# mcu.net
KiCad netlist of a schematic drawn in Altium Designer
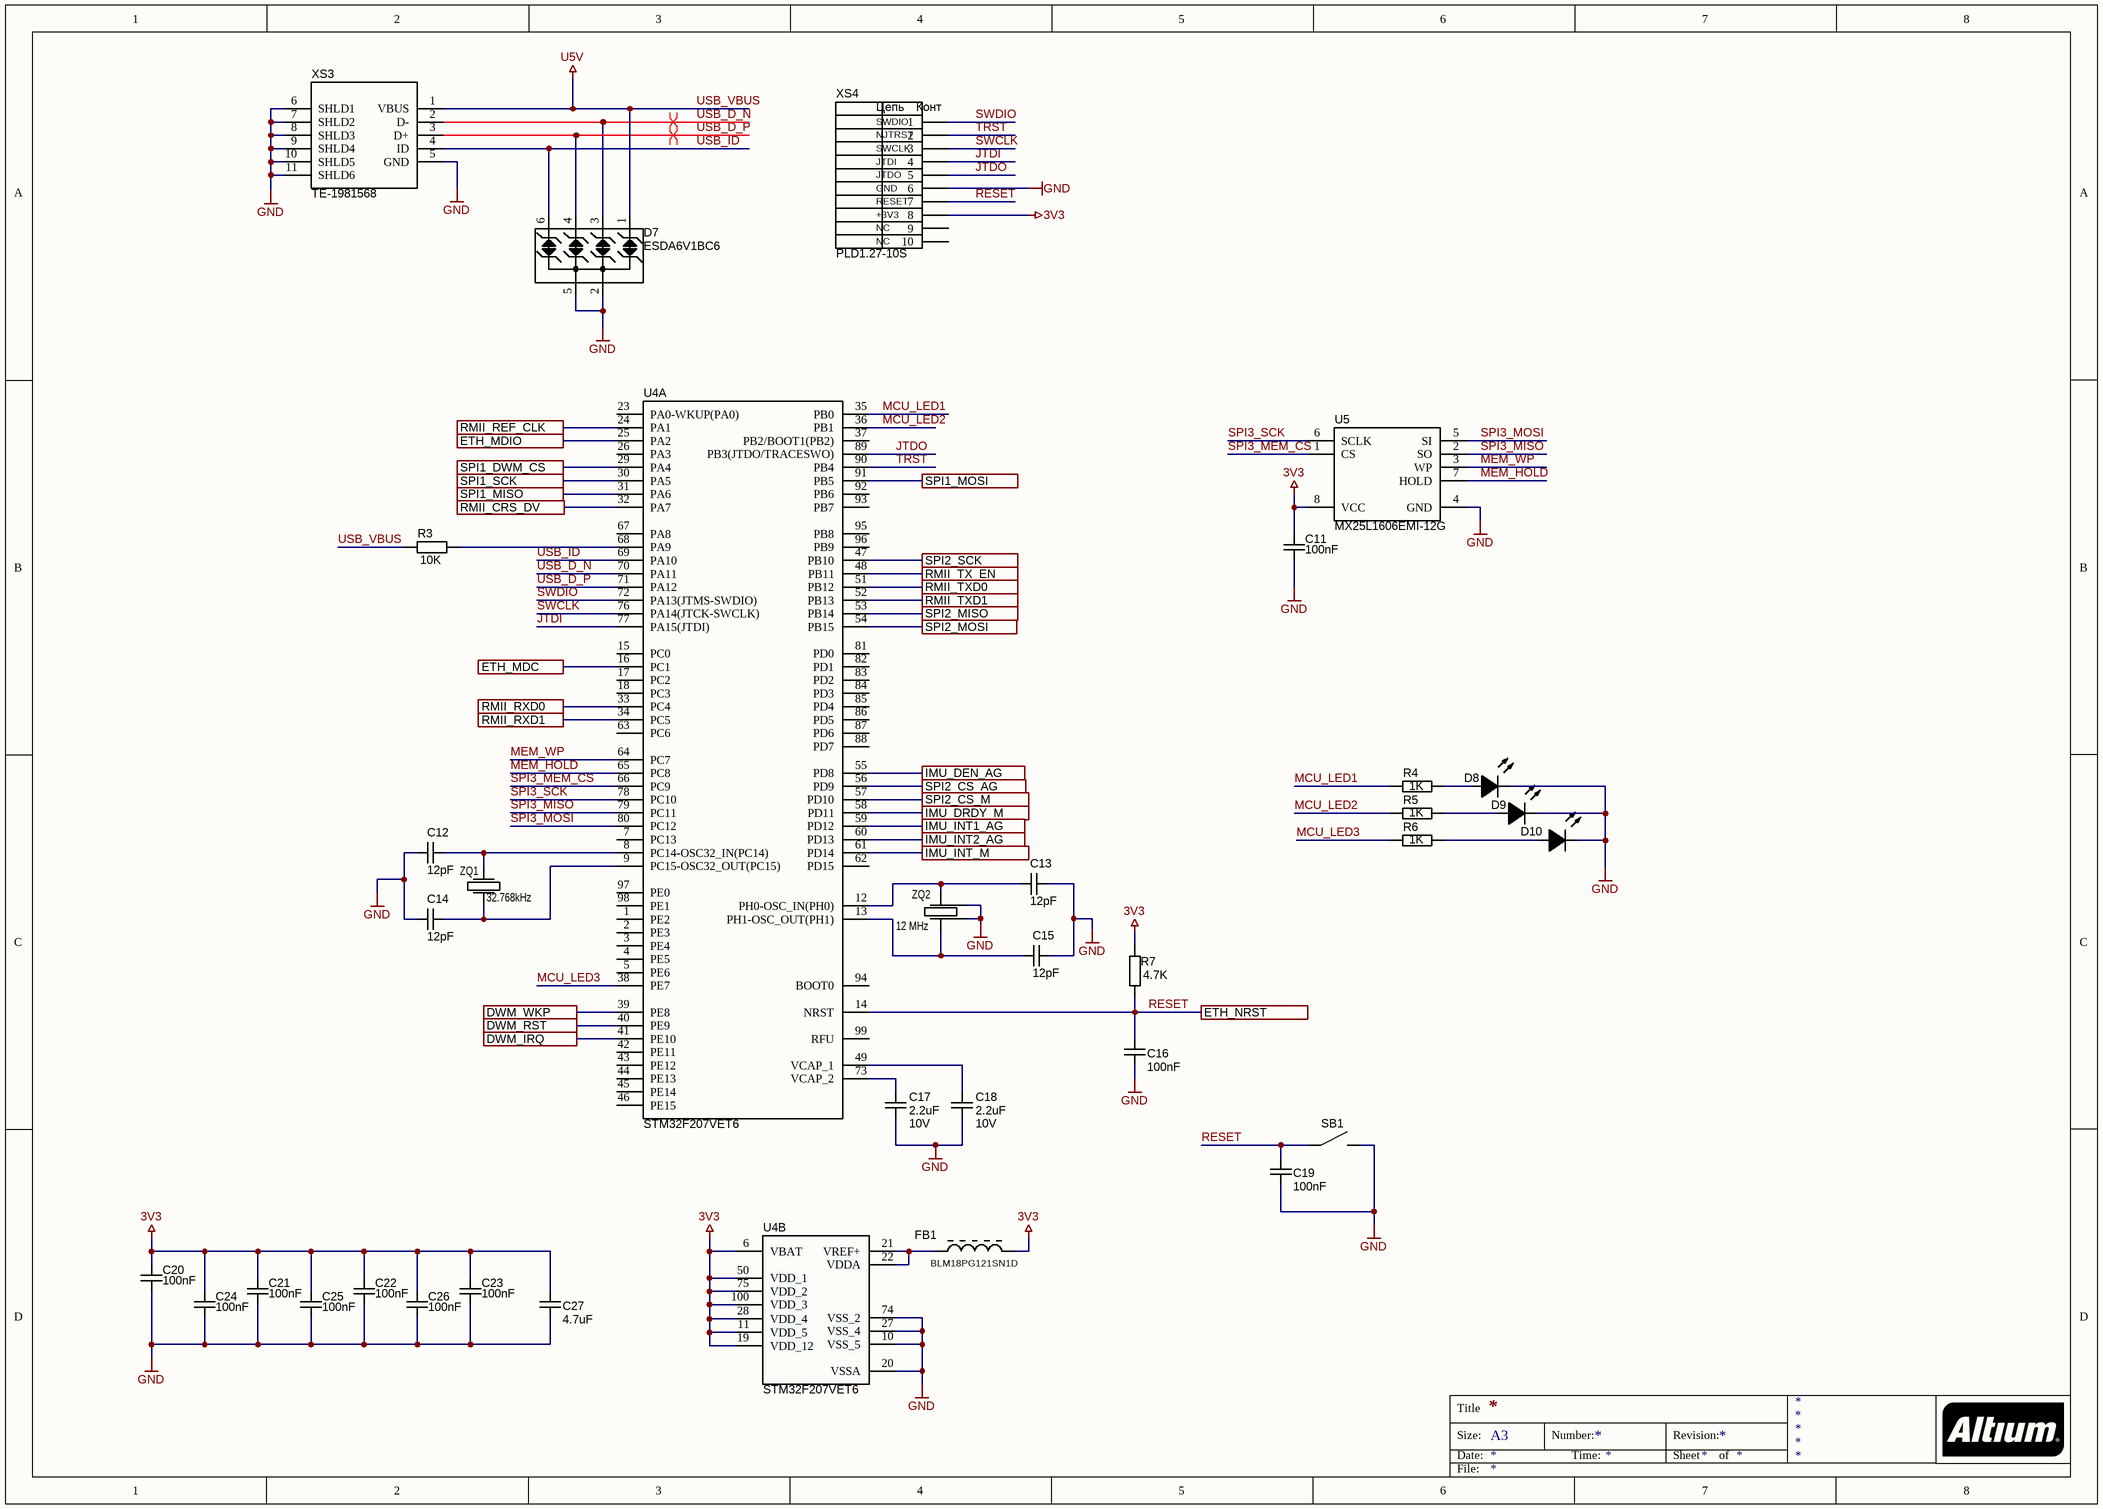
[diagram p0: mcu.SchDoc]

(export (version "E")
  (design (tool "Eeschema 10.0.6"))
  (components
    (comp (ref "C11")
      (value "100nF")
      (footprint "C0603")
      (fields (field (name "VOLTAGE") "10V") (field (name "Comment") "C0603"))
      (libsource (lib "DZ_LIB") (part "C0603"))
    )
    (comp (ref "C12")
      (value "12pF")
      (footprint "C0603")
      (fields (field (name "VOLTAGE") "*V") (field (name "Comment") "C0603"))
      (libsource (lib "DZ_LIB") (part "C0603"))
    )
    (comp (ref "C13")
      (value "12pF")
      (footprint "C0603")
      (fields (field (name "VOLTAGE") "10V") (field (name "Comment") "C0603"))
      (libsource (lib "DZ_LIB") (part "C0603"))
    )
    (comp (ref "C14")
      (value "12pF")
      (footprint "C0603")
      (fields (field (name "VOLTAGE") "*V") (field (name "Comment") "C0603"))
      (libsource (lib "DZ_LIB") (part "C0603"))
    )
    (comp (ref "C15")
      (value "12pF")
      (footprint "C0603")
      (fields (field (name "VOLTAGE") "10V") (field (name "Comment") "C0603"))
      (libsource (lib "DZ_LIB") (part "C0603"))
    )
    (comp (ref "C16")
      (value "100nF")
      (footprint "C0603")
      (fields (field (name "VOLTAGE") "10V") (field (name "Comment") "C0603"))
      (libsource (lib "DZ_LIB") (part "C0603"))
    )
    (comp (ref "C17")
      (value "2.2uF")
      (footprint "C1206(3216)")
      (fields (field (name "VOLTAGE") "10V") (field (name "Comment") "C1206"))
      (libsource (lib "DZ_LIB") (part "C1206"))
    )
    (comp (ref "C18")
      (value "2.2uF")
      (footprint "C1206(3216)")
      (fields (field (name "VOLTAGE") "10V") (field (name "Comment") "C1206"))
      (libsource (lib "DZ_LIB") (part "C1206"))
    )
    (comp (ref "C19")
      (value "100nF")
      (footprint "C0603")
      (fields (field (name "VOLTAGE") "10V") (field (name "Comment") "C0603"))
      (libsource (lib "DZ_LIB") (part "C0603"))
    )
    (comp (ref "C20")
      (value "100nF")
      (footprint "C0603")
      (fields (field (name "VOLTAGE") "10V") (field (name "Comment") "C0603"))
      (libsource (lib "DZ_LIB") (part "C0603"))
    )
    (comp (ref "C21")
      (value "100nF")
      (footprint "C0603")
      (fields (field (name "VOLTAGE") "10V") (field (name "Comment") "C0603"))
      (libsource (lib "DZ_LIB") (part "C0603"))
    )
    (comp (ref "C22")
      (value "100nF")
      (footprint "C0603")
      (fields (field (name "VOLTAGE") "10V") (field (name "Comment") "C0603"))
      (libsource (lib "DZ_LIB") (part "C0603"))
    )
    (comp (ref "C23")
      (value "100nF")
      (footprint "C0603")
      (fields (field (name "VOLTAGE") "10V") (field (name "Comment") "C0603"))
      (libsource (lib "DZ_LIB") (part "C0603"))
    )
    (comp (ref "C24")
      (value "100nF")
      (footprint "C0603")
      (fields (field (name "VOLTAGE") "10V") (field (name "Comment") "C0603"))
      (libsource (lib "DZ_LIB") (part "C0603"))
    )
    (comp (ref "C25")
      (value "100nF")
      (footprint "C0603")
      (fields (field (name "VOLTAGE") "10V") (field (name "Comment") "C0603"))
      (libsource (lib "DZ_LIB") (part "C0603"))
    )
    (comp (ref "C26")
      (value "100nF")
      (footprint "C0603")
      (fields (field (name "VOLTAGE") "10V") (field (name "Comment") "C0603"))
      (libsource (lib "DZ_LIB") (part "C0603"))
    )
    (comp (ref "C27")
      (value "4.7uF")
      (footprint "C0603")
      (fields (field (name "VOLTAGE") "10V") (field (name "Comment") "C0603"))
      (libsource (lib "DZ_LIB") (part "C0603"))
    )
    (comp (ref "D7")
      (value "ESDA6V1BC6")
      (footprint "SOT-23-6")
      (description "4-line ESD protection")
      (libsource (lib "DZ_LIB") (part "ESDA6V1BC6"))
    )
    (comp (ref "D8")
      (value "LED0805")
      (footprint "LED0805")
      (description "LED SMD 0805 K1A2")
      (libsource (lib "DZ_LIB") (part "LED0805"))
    )
    (comp (ref "D9")
      (value "LED0805")
      (footprint "LED0805")
      (description "LED SMD 0805 K1A2")
      (libsource (lib "DZ_LIB") (part "LED0805"))
    )
    (comp (ref "D10")
      (value "LED0805")
      (footprint "LED0805")
      (description "LED SMD 0805 K1A2")
      (libsource (lib "DZ_LIB") (part "LED0805"))
    )
    (comp (ref "FB1")
      (value "BLM18PG121SN1D")
      (footprint "BLM18")
      (description "Ferrite Bead 0603")
      (libsource (lib "DZ_LIB") (part "BLM18"))
    )
    (comp (ref "R3") (value "10K") (footprint "SMD0603") (libsource (lib "DZ_LIB") (part "R0603")))
    (comp (ref "R4") (value "1K") (footprint "SMD0603") (libsource (lib "") (part "R0603_1")))
    (comp (ref "R5") (value "1K") (footprint "SMD0603") (libsource (lib "") (part "R0603_1")))
    (comp (ref "R6") (value "1K") (footprint "SMD0603") (libsource (lib "") (part "R0603_1")))
    (comp (ref "R7")
      (value "4.7K")
      (footprint "SMD0603")
      (fields (field (name "Comment") "R0603"))
      (libsource (lib "") (part "R0603_2"))
    )
    (comp (ref "SB1")
      (value "FSMSM")
      (footprint "FSMSM-2")
      (description "SMD Switch 2-Leads")
      (libsource (lib "DZ_LIB") (part "FSMSM"))
    )
    (comp (ref "U4")
      (value "STM32F207VET6")
      (footprint "STM-LQFP100_V")
      (libsource (lib "DZ_LIB") (part "STM32F207VET6"))
    )
    (comp (ref "U5")
      (value "MX25L1606EMI-12G")
      (footprint "SOP-8")
      (description "FLASH 16M SPI 86MHZ 16SOP")
      (libsource (lib "DZ_LIB") (part "MX25L1606EMI-12G"))
    )
    (comp (ref "XS3")
      (value "TE-1981568")
      (footprint "TECO-1981568-5_V")
      (libsource (lib "DZ_LIB") (part "USB-Micro B"))
    )
    (comp (ref "XS4")
      (value "PLD1.27-10S")
      (footprint "PLD1.27-10S")
      (libsource (lib "DZ_LIB") (part "PLD1.27-10-MCU"))
    )
    (comp (ref "ZQ1")
      (value "32.768kHz")
      (footprint "DST210A")
      (description "DST210A")
      (libsource (lib "DZ_LIB") (part "Crystal"))
    )
    (comp (ref "ZQ2")
      (value "12 MHz")
      (footprint "NX3225")
      (description "DSX321G")
      (libsource (lib "DZ_LIB") (part "Crystal_4"))
    )
  )
  (nets
    (net (code "1") (name "/DWM_IRQ") (class "Default")
      (node (ref "U4") (pin "41") (pinfunction "PE10_41") (pintype "passive"))
    )
    (net (code "2") (name "/DWM_RST") (class "Default")
      (node (ref "U4") (pin "40") (pinfunction "PE9_40") (pintype "passive"))
    )
    (net (code "3") (name "/DWM_WKP") (class "Default")
      (node (ref "U4") (pin "39") (pinfunction "PE8_39") (pintype "passive"))
    )
    (net (code "4") (name "/ETH_MDC") (class "Default")
      (node (ref "U4") (pin "16") (pinfunction "PC1_16") (pintype "passive"))
    )
    (net (code "5") (name "/ETH_MDIO") (class "Default")
      (node (ref "U4") (pin "25") (pinfunction "PA2_25") (pintype "passive"))
    )
    (net (code "6") (name "/IMU_DEN_AG") (class "Default")
      (node (ref "U4") (pin "55") (pinfunction "PD8_55") (pintype "passive"))
    )
    (net (code "7") (name "/IMU_DRDY_M") (class "Default")
      (node (ref "U4") (pin "58") (pinfunction "PD11_58") (pintype "passive"))
    )
    (net (code "8") (name "/IMU_INT1_AG") (class "Default")
      (node (ref "U4") (pin "59") (pinfunction "PD12_59") (pintype "passive"))
    )
    (net (code "9") (name "/IMU_INT2_AG") (class "Default")
      (node (ref "U4") (pin "60") (pinfunction "PD13_60") (pintype "passive"))
    )
    (net (code "10") (name "/IMU_INT_M") (class "Default")
      (node (ref "U4") (pin "61") (pinfunction "PD14_61") (pintype "passive"))
    )
    (net (code "11") (name "/JTDI") (class "Default")
      (node (ref "U4") (pin "77") (pinfunction "PA15(JTDI)_77") (pintype "passive"))
      (node (ref "XS4") (pin "4") (pinfunction "4_4") (pintype "passive"))
    )
    (net (code "12") (name "/JTDO") (class "Default")
      (node (ref "U4") (pin "89") (pinfunction "PB3(JTDO/TRACESWO)_89") (pintype "passive"))
      (node (ref "XS4") (pin "5") (pinfunction "5_5") (pintype "passive"))
    )
    (net (code "13") (name "/MCU_LED1") (class "Default")
      (node (ref "R4") (pin "2") (pinfunction "2_2") (pintype "passive"))
      (node (ref "U4") (pin "35") (pinfunction "PB0_35") (pintype "passive"))
    )
    (net (code "14") (name "/MCU_LED2") (class "Default")
      (node (ref "R5") (pin "2") (pinfunction "2_2") (pintype "passive"))
      (node (ref "U4") (pin "36") (pinfunction "PB1_36") (pintype "passive"))
    )
    (net (code "15") (name "/MCU_LED3") (class "Default")
      (node (ref "R6") (pin "2") (pinfunction "2_2") (pintype "passive"))
      (node (ref "U4") (pin "38") (pinfunction "PE7_38") (pintype "passive"))
    )
    (net (code "16") (name "/MEM_HOLD") (class "Default")
      (node (ref "U4") (pin "65") (pinfunction "PC8_65") (pintype "passive"))
      (node (ref "U5") (pin "7") (pinfunction "HOLD_7") (pintype "passive"))
    )
    (net (code "17") (name "/MEM_WP") (class "Default")
      (node (ref "U4") (pin "64") (pinfunction "PC7_64") (pintype "passive"))
      (node (ref "U5") (pin "3") (pinfunction "WP_3") (pintype "passive"))
    )
    (net (code "18") (name "/RESET") (class "Default")
      (node (ref "C16") (pin "2") (pinfunction "2_2") (pintype "passive"))
      (node (ref "C19") (pin "2") (pinfunction "2_2") (pintype "passive"))
      (node (ref "R7") (pin "1") (pinfunction "1_1") (pintype "passive"))
      (node (ref "SB1") (pin "1") (pinfunction "1_1") (pintype "passive"))
      (node (ref "U4") (pin "14") (pinfunction "NRST_14") (pintype "passive"))
      (node (ref "XS4") (pin "7") (pinfunction "7_7") (pintype "passive"))
    )
    (net (code "19") (name "/RMII_CRS_DV") (class "Default")
      (node (ref "U4") (pin "32") (pinfunction "PA7_32") (pintype "passive"))
    )
    (net (code "20") (name "/RMII_REF_CLK") (class "Default")
      (node (ref "U4") (pin "24") (pinfunction "PA1_24") (pintype "passive"))
    )
    (net (code "21") (name "/RMII_RXD0") (class "Default")
      (node (ref "U4") (pin "33") (pinfunction "PC4_33") (pintype "passive"))
    )
    (net (code "22") (name "/RMII_RXD1") (class "Default")
      (node (ref "U4") (pin "34") (pinfunction "PC5_34") (pintype "passive"))
    )
    (net (code "23") (name "/RMII_TXD0") (class "Default")
      (node (ref "U4") (pin "51") (pinfunction "PB12_51") (pintype "passive"))
    )
    (net (code "24") (name "/RMII_TXD1") (class "Default")
      (node (ref "U4") (pin "52") (pinfunction "PB13_52") (pintype "passive"))
    )
    (net (code "25") (name "/RMII_TX_EN") (class "Default")
      (node (ref "U4") (pin "48") (pinfunction "PB11_48") (pintype "passive"))
    )
    (net (code "26") (name "/SPI1_DWM_CS") (class "Default")
      (node (ref "U4") (pin "29") (pinfunction "PA4_29") (pintype "passive"))
    )
    (net (code "27") (name "/SPI1_MISO") (class "Default")
      (node (ref "U4") (pin "31") (pinfunction "PA6_31") (pintype "passive"))
    )
    (net (code "28") (name "/SPI1_MOSI") (class "Default")
      (node (ref "U4") (pin "91") (pinfunction "PB5_91") (pintype "passive"))
    )
    (net (code "29") (name "/SPI1_SCK") (class "Default")
      (node (ref "U4") (pin "30") (pinfunction "PA5_30") (pintype "passive"))
    )
    (net (code "30") (name "/SPI2_CS_AG") (class "Default")
      (node (ref "U4") (pin "56") (pinfunction "PD9_56") (pintype "passive"))
    )
    (net (code "31") (name "/SPI2_CS_M") (class "Default")
      (node (ref "U4") (pin "57") (pinfunction "PD10_57") (pintype "passive"))
    )
    (net (code "32") (name "/SPI2_MISO") (class "Default")
      (node (ref "U4") (pin "53") (pinfunction "PB14_53") (pintype "passive"))
    )
    (net (code "33") (name "/SPI2_MOSI") (class "Default")
      (node (ref "U4") (pin "54") (pinfunction "PB15_54") (pintype "passive"))
    )
    (net (code "34") (name "/SPI2_SCK") (class "Default")
      (node (ref "U4") (pin "47") (pinfunction "PB10_47") (pintype "passive"))
    )
    (net (code "35") (name "/SPI3_MEM_CS") (class "Default")
      (node (ref "U4") (pin "66") (pinfunction "PC9_66") (pintype "passive"))
      (node (ref "U5") (pin "1") (pinfunction "CS_1") (pintype "passive"))
    )
    (net (code "36") (name "/SPI3_MISO") (class "Default")
      (node (ref "U4") (pin "79") (pinfunction "PC11_79") (pintype "passive"))
      (node (ref "U5") (pin "2") (pinfunction "SO_2") (pintype "passive"))
    )
    (net (code "37") (name "/SPI3_MOSI") (class "Default")
      (node (ref "U4") (pin "80") (pinfunction "PC12_80") (pintype "passive"))
      (node (ref "U5") (pin "5") (pinfunction "SI_5") (pintype "passive"))
    )
    (net (code "38") (name "/SPI3_SCK") (class "Default")
      (node (ref "U4") (pin "78") (pinfunction "PC10_78") (pintype "passive"))
      (node (ref "U5") (pin "6") (pinfunction "SCLK_6") (pintype "passive"))
    )
    (net (code "39") (name "/SWCLK") (class "Default")
      (node (ref "U4") (pin "76") (pinfunction "PA14(JTCK-SWCLK)_76") (pintype "passive"))
      (node (ref "XS4") (pin "3") (pinfunction "3_3") (pintype "passive"))
    )
    (net (code "40") (name "/SWDIO") (class "Default")
      (node (ref "U4") (pin "72") (pinfunction "PA13(JTMS-SWDIO)_72") (pintype "passive"))
      (node (ref "XS4") (pin "1") (pinfunction "1_1") (pintype "passive"))
    )
    (net (code "41") (name "/TRST") (class "Default")
      (node (ref "U4") (pin "90") (pinfunction "PB4_90") (pintype "passive"))
      (node (ref "XS4") (pin "2") (pinfunction "2_2") (pintype "passive"))
    )
    (net (code "42") (name "/USB_D_N") (class "Default")
      (node (ref "D7") (pin "3") (pinfunction "GND_3") (pintype "passive"))
      (node (ref "U4") (pin "70") (pinfunction "PA11_70") (pintype "passive"))
      (node (ref "XS3") (pin "2") (pinfunction "D-_2") (pintype "passive"))
    )
    (net (code "43") (name "/USB_D_P") (class "Default")
      (node (ref "D7") (pin "4") (pinfunction "IO3_4") (pintype "passive"))
      (node (ref "U4") (pin "71") (pinfunction "PA12_71") (pintype "passive"))
      (node (ref "XS3") (pin "3") (pinfunction "D+_3") (pintype "passive"))
    )
    (net (code "44") (name "/USB_ID") (class "Default")
      (node (ref "D7") (pin "6") (pinfunction "NC_6") (pintype "passive"))
      (node (ref "U4") (pin "69") (pinfunction "PA10_69") (pintype "passive"))
      (node (ref "XS3") (pin "4") (pinfunction "ID_4") (pintype "passive"))
    )
    (net (code "45") (name "3V3") (class "Default")
      (node (ref "C11") (pin "2") (pinfunction "2_2") (pintype "passive"))
      (node (ref "C20") (pin "2") (pinfunction "2_2") (pintype "passive"))
      (node (ref "C21") (pin "2") (pinfunction "2_2") (pintype "passive"))
      (node (ref "C22") (pin "2") (pinfunction "2_2") (pintype "passive"))
      (node (ref "C23") (pin "2") (pinfunction "2_2") (pintype "passive"))
      (node (ref "C24") (pin "2") (pinfunction "2_2") (pintype "passive"))
      (node (ref "C25") (pin "2") (pinfunction "2_2") (pintype "passive"))
      (node (ref "C26") (pin "2") (pinfunction "2_2") (pintype "passive"))
      (node (ref "C27") (pin "1") (pinfunction "1_1") (pintype "passive"))
      (node (ref "FB1") (pin "2") (pinfunction "2_2") (pintype "passive"))
      (node (ref "R7") (pin "2") (pinfunction "2_2") (pintype "passive"))
      (node (ref "U4") (pin "100") (pinfunction "VDD_3_100") (pintype "power_in"))
      (node (ref "U4") (pin "11") (pinfunction "VDD_5_11") (pintype "power_in"))
      (node (ref "U4") (pin "19") (pinfunction "VDD_12_19") (pintype "power_in"))
      (node (ref "U4") (pin "28") (pinfunction "VDD_4_28") (pintype "power_in"))
      (node (ref "U4") (pin "50") (pinfunction "VDD_1_50") (pintype "power_in"))
      (node (ref "U4") (pin "6") (pinfunction "VBAT_6") (pintype "power_in"))
      (node (ref "U4") (pin "75") (pinfunction "VDD_2_75") (pintype "power_in"))
      (node (ref "U5") (pin "8") (pinfunction "VCC_8") (pintype "passive"))
      (node (ref "XS4") (pin "8") (pinfunction "8_8") (pintype "passive"))
    )
    (net (code "46") (name "GND") (class "Default")
      (node (ref "C11") (pin "1") (pinfunction "1_1") (pintype "passive"))
      (node (ref "C12") (pin "1") (pinfunction "1_1") (pintype "passive"))
      (node (ref "C13") (pin "2") (pinfunction "2_2") (pintype "passive"))
      (node (ref "C14") (pin "1") (pinfunction "1_1") (pintype "passive"))
      (node (ref "C15") (pin "2") (pinfunction "2_2") (pintype "passive"))
      (node (ref "C16") (pin "1") (pinfunction "1_1") (pintype "passive"))
      (node (ref "C17") (pin "1") (pinfunction "1_1") (pintype "passive"))
      (node (ref "C18") (pin "1") (pinfunction "1_1") (pintype "passive"))
      (node (ref "C19") (pin "1") (pinfunction "1_1") (pintype "passive"))
      (node (ref "C20") (pin "1") (pinfunction "1_1") (pintype "passive"))
      (node (ref "C21") (pin "1") (pinfunction "1_1") (pintype "passive"))
      (node (ref "C22") (pin "1") (pinfunction "1_1") (pintype "passive"))
      (node (ref "C23") (pin "1") (pinfunction "1_1") (pintype "passive"))
      (node (ref "C24") (pin "1") (pinfunction "1_1") (pintype "passive"))
      (node (ref "C25") (pin "1") (pinfunction "1_1") (pintype "passive"))
      (node (ref "C26") (pin "1") (pinfunction "1_1") (pintype "passive"))
      (node (ref "C27") (pin "2") (pinfunction "2_2") (pintype "passive"))
      (node (ref "D10") (pin "1") (pinfunction "K_1") (pintype "passive"))
      (node (ref "D7") (pin "2") (pinfunction "IO2_2") (pintype "passive"))
      (node (ref "D7") (pin "5") (pinfunction "IO4_5") (pintype "passive"))
      (node (ref "D8") (pin "1") (pinfunction "K_1") (pintype "passive"))
      (node (ref "D9") (pin "1") (pinfunction "K_1") (pintype "passive"))
      (node (ref "SB1") (pin "2") (pinfunction "2_2") (pintype "passive"))
      (node (ref "U4") (pin "10") (pinfunction "VSS_5_10") (pintype "power_in"))
      (node (ref "U4") (pin "20") (pinfunction "VSSA_20") (pintype "power_in"))
      (node (ref "U4") (pin "27") (pinfunction "VSS_4_27") (pintype "power_in"))
      (node (ref "U4") (pin "74") (pinfunction "VSS_2_74") (pintype "power_in"))
      (node (ref "U5") (pin "4") (pinfunction "GND_4") (pintype "passive"))
      (node (ref "XS3") (pin "10") (pinfunction "SHLD5_10") (pintype "passive"))
      (node (ref "XS3") (pin "11") (pinfunction "SHLD6_11") (pintype "passive"))
      (node (ref "XS3") (pin "5") (pinfunction "GND_5") (pintype "passive"))
      (node (ref "XS3") (pin "6") (pinfunction "SHLD1_6") (pintype "passive"))
      (node (ref "XS3") (pin "7") (pinfunction "SHLD2_7") (pintype "passive"))
      (node (ref "XS3") (pin "8") (pinfunction "SHLD3_8") (pintype "passive"))
      (node (ref "XS3") (pin "9") (pinfunction "SHLD4_9") (pintype "passive"))
      (node (ref "XS4") (pin "6") (pinfunction "6_6") (pintype "passive"))
      (node (ref "ZQ2") (pin "2") (pinfunction "2_2") (pintype "passive"))
      (node (ref "ZQ2") (pin "4") (pinfunction "4_4") (pintype "passive"))
    )
    (net (code "47") (name "Net-(D8-A)") (class "Default")
      (node (ref "D8") (pin "2") (pinfunction "A_2") (pintype "passive"))
      (node (ref "R4") (pin "1") (pinfunction "1_1") (pintype "passive"))
    )
    (net (code "48") (name "Net-(D9-A)") (class "Default")
      (node (ref "D9") (pin "2") (pinfunction "A_2") (pintype "passive"))
      (node (ref "R5") (pin "1") (pinfunction "1_1") (pintype "passive"))
    )
    (net (code "49") (name "Net-(D10-A)") (class "Default")
      (node (ref "D10") (pin "2") (pinfunction "A_2") (pintype "passive"))
      (node (ref "R6") (pin "1") (pinfunction "1_1") (pintype "passive"))
    )
    (net (code "50") (name "Net-(U4A-PA9)") (class "Default")
      (node (ref "R3") (pin "2") (pinfunction "2_2") (pintype "passive"))
      (node (ref "U4") (pin "68") (pinfunction "PA9_68") (pintype "passive"))
    )
    (net (code "51") (name "Net-(U4A-PC14-OSC32_IN(PC14))") (class "Default")
      (node (ref "C12") (pin "2") (pinfunction "2_2") (pintype "passive"))
      (node (ref "U4") (pin "8") (pinfunction "PC14-OSC32_IN(PC14)_8") (pintype "passive"))
      (node (ref "ZQ1") (pin "2") (pinfunction "OSC2_2") (pintype "passive"))
    )
    (net (code "52") (name "Net-(U4A-PC15-OSC32_OUT(PC15))") (class "Default")
      (node (ref "C14") (pin "2") (pinfunction "2_2") (pintype "passive"))
      (node (ref "U4") (pin "9") (pinfunction "PC15-OSC32_OUT(PC15)_9") (pintype "passive"))
      (node (ref "ZQ1") (pin "1") (pinfunction "OSC1_1") (pintype "passive"))
    )
    (net (code "53") (name "Net-(U4A-PH0-OSC_IN(PH0))") (class "Default")
      (node (ref "C13") (pin "1") (pinfunction "1_1") (pintype "passive"))
      (node (ref "U4") (pin "12") (pinfunction "PH0-OSC_IN(PH0)_12") (pintype "passive"))
      (node (ref "ZQ2") (pin "3") (pinfunction "3_3") (pintype "passive"))
    )
    (net (code "54") (name "Net-(U4A-PH1-OSC_OUT(PH1))") (class "Default")
      (node (ref "C15") (pin "1") (pinfunction "1_1") (pintype "passive"))
      (node (ref "U4") (pin "13") (pinfunction "PH1-OSC_OUT(PH1)_13") (pintype "passive"))
      (node (ref "ZQ2") (pin "1") (pinfunction "1_1") (pintype "passive"))
    )
    (net (code "55") (name "Net-(U4A-VCAP_1)") (class "Default")
      (node (ref "C18") (pin "2") (pinfunction "2_2") (pintype "passive"))
      (node (ref "U4") (pin "49") (pinfunction "VCAP_1_49") (pintype "passive"))
    )
    (net (code "56") (name "Net-(U4A-VCAP_2)") (class "Default")
      (node (ref "C17") (pin "2") (pinfunction "2_2") (pintype "passive"))
      (node (ref "U4") (pin "73") (pinfunction "VCAP_2_73") (pintype "passive"))
    )
    (net (code "57") (name "Net-(U4B-VDDA)") (class "Default")
      (node (ref "FB1") (pin "1") (pinfunction "1_1") (pintype "passive"))
      (node (ref "U4") (pin "21") (pinfunction "VREF+_21") (pintype "power_in"))
      (node (ref "U4") (pin "22") (pinfunction "VDDA_22") (pintype "power_in"))
    )
    (net (code "58") (name "U5V") (class "Default")
      (node (ref "D7") (pin "1") (pinfunction "IO1_1") (pintype "passive"))
      (node (ref "R3") (pin "1") (pinfunction "1_1") (pintype "passive"))
      (node (ref "XS3") (pin "1") (pinfunction "VBUS_1") (pintype "passive"))
    )
    (net (code "59") (name "unconnected-(U4A-BOOT0-Pad94)") (class "Default")
      (node (ref "U4") (pin "94") (pinfunction "BOOT0_94") (pintype "passive"))
    )
    (net (code "60") (name "unconnected-(U4A-PA0-WKUP(PA0)-Pad23)") (class "Default")
      (node (ref "U4") (pin "23") (pinfunction "PA0-WKUP(PA0)_23") (pintype "passive"))
    )
    (net (code "61") (name "unconnected-(U4A-PA3-Pad26)") (class "Default")
      (node (ref "U4") (pin "26") (pinfunction "PA3_26") (pintype "passive"))
    )
    (net (code "62") (name "unconnected-(U4A-PA8-Pad67)") (class "Default")
      (node (ref "U4") (pin "67") (pinfunction "PA8_67") (pintype "passive"))
    )
    (net (code "63") (name "unconnected-(U4A-PB2{slash}BOOT1(PB2)-Pad37)") (class "Default")
      (node (ref "U4") (pin "37") (pinfunction "PB2/BOOT1(PB2)_37") (pintype "passive"))
    )
    (net (code "64") (name "unconnected-(U4A-PB6-Pad92)") (class "Default")
      (node (ref "U4") (pin "92") (pinfunction "PB6_92") (pintype "passive"))
    )
    (net (code "65") (name "unconnected-(U4A-PB7-Pad93)") (class "Default")
      (node (ref "U4") (pin "93") (pinfunction "PB7_93") (pintype "passive"))
    )
    (net (code "66") (name "unconnected-(U4A-PB8-Pad95)") (class "Default")
      (node (ref "U4") (pin "95") (pinfunction "PB8_95") (pintype "passive"))
    )
    (net (code "67") (name "unconnected-(U4A-PB9-Pad96)") (class "Default")
      (node (ref "U4") (pin "96") (pinfunction "PB9_96") (pintype "passive"))
    )
    (net (code "68") (name "unconnected-(U4A-PC0-Pad15)") (class "Default")
      (node (ref "U4") (pin "15") (pinfunction "PC0_15") (pintype "passive"))
    )
    (net (code "69") (name "unconnected-(U4A-PC2-Pad17)") (class "Default")
      (node (ref "U4") (pin "17") (pinfunction "PC2_17") (pintype "passive"))
    )
    (net (code "70") (name "unconnected-(U4A-PC3-Pad18)") (class "Default")
      (node (ref "U4") (pin "18") (pinfunction "PC3_18") (pintype "passive"))
    )
    (net (code "71") (name "unconnected-(U4A-PC6-Pad63)") (class "Default")
      (node (ref "U4") (pin "63") (pinfunction "PC6_63") (pintype "passive"))
    )
    (net (code "72") (name "unconnected-(U4A-PC13-Pad7)") (class "Default")
      (node (ref "U4") (pin "7") (pinfunction "PC13_7") (pintype "passive"))
    )
    (net (code "73") (name "unconnected-(U4A-PD0-Pad81)") (class "Default")
      (node (ref "U4") (pin "81") (pinfunction "PD0_81") (pintype "passive"))
    )
    (net (code "74") (name "unconnected-(U4A-PD1-Pad82)") (class "Default")
      (node (ref "U4") (pin "82") (pinfunction "PD1_82") (pintype "passive"))
    )
    (net (code "75") (name "unconnected-(U4A-PD2-Pad83)") (class "Default")
      (node (ref "U4") (pin "83") (pinfunction "PD2_83") (pintype "passive"))
    )
    (net (code "76") (name "unconnected-(U4A-PD3-Pad84)") (class "Default")
      (node (ref "U4") (pin "84") (pinfunction "PD3_84") (pintype "passive"))
    )
    (net (code "77") (name "unconnected-(U4A-PD4-Pad85)") (class "Default")
      (node (ref "U4") (pin "85") (pinfunction "PD4_85") (pintype "passive"))
    )
    (net (code "78") (name "unconnected-(U4A-PD5-Pad86)") (class "Default")
      (node (ref "U4") (pin "86") (pinfunction "PD5_86") (pintype "passive"))
    )
    (net (code "79") (name "unconnected-(U4A-PD6-Pad87)") (class "Default")
      (node (ref "U4") (pin "87") (pinfunction "PD6_87") (pintype "passive"))
    )
    (net (code "80") (name "unconnected-(U4A-PD7-Pad88)") (class "Default")
      (node (ref "U4") (pin "88") (pinfunction "PD7_88") (pintype "passive"))
    )
    (net (code "81") (name "unconnected-(U4A-PD15-Pad62)") (class "Default")
      (node (ref "U4") (pin "62") (pinfunction "PD15_62") (pintype "passive"))
    )
    (net (code "82") (name "unconnected-(U4A-PE0-Pad97)") (class "Default")
      (node (ref "U4") (pin "97") (pinfunction "PE0_97") (pintype "passive"))
    )
    (net (code "83") (name "unconnected-(U4A-PE1-Pad98)") (class "Default")
      (node (ref "U4") (pin "98") (pinfunction "PE1_98") (pintype "passive"))
    )
    (net (code "84") (name "unconnected-(U4A-PE2-Pad1)") (class "Default")
      (node (ref "U4") (pin "1") (pinfunction "PE2_1") (pintype "passive"))
    )
    (net (code "85") (name "unconnected-(U4A-PE3-Pad2)") (class "Default")
      (node (ref "U4") (pin "2") (pinfunction "PE3_2") (pintype "passive"))
    )
    (net (code "86") (name "unconnected-(U4A-PE4-Pad3)") (class "Default")
      (node (ref "U4") (pin "3") (pinfunction "PE4_3") (pintype "passive"))
    )
    (net (code "87") (name "unconnected-(U4A-PE5-Pad4)") (class "Default")
      (node (ref "U4") (pin "4") (pinfunction "PE5_4") (pintype "passive"))
    )
    (net (code "88") (name "unconnected-(U4A-PE6-Pad5)") (class "Default")
      (node (ref "U4") (pin "5") (pinfunction "PE6_5") (pintype "passive"))
    )
    (net (code "89") (name "unconnected-(U4A-PE11-Pad42)") (class "Default")
      (node (ref "U4") (pin "42") (pinfunction "PE11_42") (pintype "passive"))
    )
    (net (code "90") (name "unconnected-(U4A-PE12-Pad43)") (class "Default")
      (node (ref "U4") (pin "43") (pinfunction "PE12_43") (pintype "passive"))
    )
    (net (code "91") (name "unconnected-(U4A-PE13-Pad44)") (class "Default")
      (node (ref "U4") (pin "44") (pinfunction "PE13_44") (pintype "passive"))
    )
    (net (code "92") (name "unconnected-(U4A-PE14-Pad45)") (class "Default")
      (node (ref "U4") (pin "45") (pinfunction "PE14_45") (pintype "passive"))
    )
    (net (code "93") (name "unconnected-(U4A-PE15-Pad46)") (class "Default")
      (node (ref "U4") (pin "46") (pinfunction "PE15_46") (pintype "passive"))
    )
    (net (code "94") (name "unconnected-(U4A-RFU-Pad99)") (class "Default")
      (node (ref "U4") (pin "99") (pinfunction "RFU_99") (pintype "passive"))
    )
    (net (code "95") (name "unconnected-(XS4-Pad9)") (class "Default")
      (node (ref "XS4") (pin "9") (pinfunction "9_9") (pintype "passive"))
    )
    (net (code "96") (name "unconnected-(XS4-Pad10)") (class "Default")
      (node (ref "XS4") (pin "10") (pinfunction "10_10") (pintype "passive"))
    )
  )
)
